# 04_-_SIM800C.net
KiCad netlist of a schematic drawn in Altium Designer
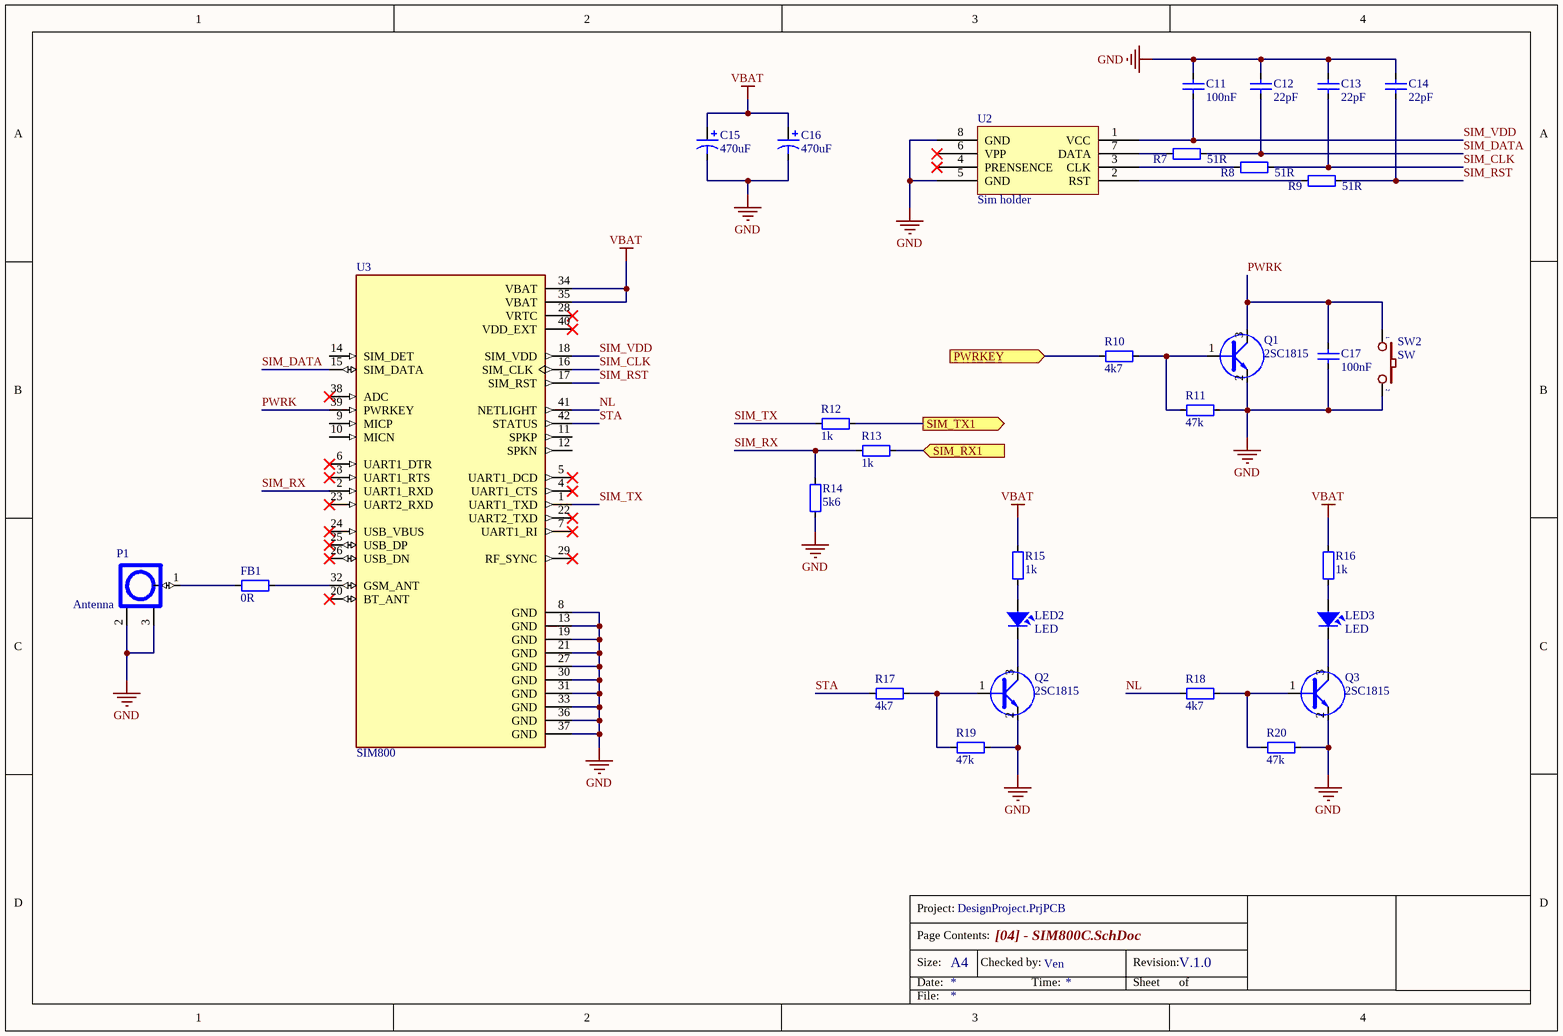
[diagram p0: [04] - SIM800C.SchDoc]

(export (version "E")
  (design (tool "Eeschema 10.0.6"))
  (components
    (comp (ref "C11")
      (value "100nF")
      (footprint "CAP_0603")
      (description "Capacitor")
      (fields (field (name "PUBLISHER") "Altium Limited"))
      (libsource (lib "My Library") (part "CapSMD"))
    )
    (comp (ref "C12")
      (value "22pF")
      (footprint "CAP_0603")
      (description "Capacitor")
      (fields (field (name "PUBLISHER") "Altium Limited"))
      (libsource (lib "My Library") (part "CapSMD"))
    )
    (comp (ref "C13")
      (value "22pF")
      (footprint "CAP_0603")
      (description "Capacitor")
      (fields (field (name "PUBLISHER") "Altium Limited"))
      (libsource (lib "My Library") (part "CapSMD"))
    )
    (comp (ref "C14")
      (value "22pF")
      (footprint "CAP_0603")
      (description "Capacitor")
      (fields (field (name "PUBLISHER") "Altium Limited"))
      (libsource (lib "My Library") (part "CapSMD"))
    )
    (comp (ref "C15")
      (value "470uF")
      (footprint "CAP_7343")
      (description "Polarized Capacitor (Axial)")
      (fields (field (name "PUBLISHER") "Altium Limited"))
      (libsource (lib "My Library") (part "Cap Pol"))
    )
    (comp (ref "C16")
      (value "470uF")
      (footprint "CAP_7343")
      (description "Polarized Capacitor (Axial)")
      (fields (field (name "PUBLISHER") "Altium Limited"))
      (libsource (lib "My Library") (part "Cap Pol"))
    )
    (comp (ref "C17")
      (value "100nF")
      (footprint "CAP_0603")
      (description "Capacitor")
      (fields (field (name "PUBLISHER") "Altium Limited"))
      (libsource (lib "My Library") (part "CapSMD"))
    )
    (comp (ref "FB1")
      (value "0R")
      (footprint "RES-SMD-0603")
      (description "Resistor")
      (fields
        (field (name "MANUFACTURER") "Generic Components")
        (field (name "PUBLISHER") "Altium Hobart Technology Centre")
      )
      (libsource (lib "My Library") (part "Resistor - SMD"))
    )
    (comp (ref "LED2")
      (value "LED")
      (footprint "LED-0805-Green")
      (description "LED Single colour Green and Red")
      (libsource (lib "My Library") (part "LED"))
    )
    (comp (ref "LED3")
      (value "LED")
      (footprint "LED-0805-Green")
      (description "LED Single colour Green and Red")
      (libsource (lib "My Library") (part "LED"))
    )
    (comp (ref "P1")
      (value "Antenna")
      (footprint "IPXS")
      (description "Antenna GSM GPS")
      (libsource (lib "My Library") (part "IPXSx66"))
    )
    (comp (ref "Q1")
      (value "2SC1815")
      (footprint "SOT23")
      (description "NPN 600mW, ECB")
      (libsource (lib "My Library") (part "2SC1815"))
    )
    (comp (ref "Q2")
      (value "2SC1815")
      (footprint "SOT23")
      (description "NPN 600mW, ECB")
      (libsource (lib "My Library") (part "2SC1815"))
    )
    (comp (ref "Q3")
      (value "2SC1815")
      (footprint "SOT23")
      (description "NPN 600mW, ECB")
      (libsource (lib "My Library") (part "2SC1815"))
    )
    (comp (ref "R7")
      (value "51R")
      (footprint "RES-SMD-0603")
      (description "Resistor")
      (fields
        (field (name "MANUFACTURER") "Generic Components")
        (field (name "PUBLISHER") "Altium Hobart Technology Centre")
      )
      (libsource (lib "My Library") (part "Resistor - SMD"))
    )
    (comp (ref "R8")
      (value "51R")
      (footprint "RES-SMD-0603")
      (description "Resistor")
      (fields
        (field (name "MANUFACTURER") "Generic Components")
        (field (name "PUBLISHER") "Altium Hobart Technology Centre")
      )
      (libsource (lib "My Library") (part "Resistor - SMD"))
    )
    (comp (ref "R9")
      (value "51R")
      (footprint "RES-SMD-0603")
      (description "Resistor")
      (fields
        (field (name "MANUFACTURER") "Generic Components")
        (field (name "PUBLISHER") "Altium Hobart Technology Centre")
      )
      (libsource (lib "My Library") (part "Resistor - SMD"))
    )
    (comp (ref "R10")
      (value "4k7")
      (footprint "RES-SMD-0603")
      (description "Resistor")
      (fields
        (field (name "MANUFACTURER") "Generic Components")
        (field (name "PUBLISHER") "Altium Hobart Technology Centre")
      )
      (libsource (lib "My Library") (part "Resistor - SMD"))
    )
    (comp (ref "R11")
      (value "47k")
      (footprint "RES-SMD-0603")
      (description "Resistor")
      (fields
        (field (name "MANUFACTURER") "Generic Components")
        (field (name "PUBLISHER") "Altium Hobart Technology Centre")
      )
      (libsource (lib "My Library") (part "Resistor - SMD"))
    )
    (comp (ref "R12")
      (value "1k")
      (footprint "RES-SMD-0603")
      (description "Resistor")
      (fields
        (field (name "MANUFACTURER") "Generic Components")
        (field (name "PUBLISHER") "Altium Hobart Technology Centre")
      )
      (libsource (lib "My Library") (part "Resistor - SMD"))
    )
    (comp (ref "R13")
      (value "1k")
      (footprint "RES-SMD-0603")
      (description "Resistor")
      (fields
        (field (name "MANUFACTURER") "Generic Components")
        (field (name "PUBLISHER") "Altium Hobart Technology Centre")
      )
      (libsource (lib "My Library") (part "Resistor - SMD"))
    )
    (comp (ref "R14")
      (value "5k6")
      (footprint "RES-SMD-0603")
      (description "Resistor")
      (fields
        (field (name "MANUFACTURER") "Generic Components")
        (field (name "PUBLISHER") "Altium Hobart Technology Centre")
      )
      (libsource (lib "My Library") (part "Resistor - SMD"))
    )
    (comp (ref "R15")
      (value "1k")
      (footprint "RES-SMD-0603")
      (description "Resistor")
      (fields
        (field (name "MANUFACTURER") "Generic Components")
        (field (name "PUBLISHER") "Altium Hobart Technology Centre")
      )
      (libsource (lib "My Library") (part "Resistor - SMD"))
    )
    (comp (ref "R16")
      (value "1k")
      (footprint "RES-SMD-0603")
      (description "Resistor")
      (fields
        (field (name "MANUFACTURER") "Generic Components")
        (field (name "PUBLISHER") "Altium Hobart Technology Centre")
      )
      (libsource (lib "My Library") (part "Resistor - SMD"))
    )
    (comp (ref "R17")
      (value "4k7")
      (footprint "RES-SMD-0603")
      (description "Resistor")
      (fields
        (field (name "MANUFACTURER") "Generic Components")
        (field (name "PUBLISHER") "Altium Hobart Technology Centre")
      )
      (libsource (lib "My Library") (part "Resistor - SMD"))
    )
    (comp (ref "R18")
      (value "4k7")
      (footprint "RES-SMD-0603")
      (description "Resistor")
      (fields
        (field (name "MANUFACTURER") "Generic Components")
        (field (name "PUBLISHER") "Altium Hobart Technology Centre")
      )
      (libsource (lib "My Library") (part "Resistor - SMD"))
    )
    (comp (ref "R19")
      (value "47k")
      (footprint "RES-SMD-0603")
      (description "Resistor")
      (fields
        (field (name "MANUFACTURER") "Generic Components")
        (field (name "PUBLISHER") "Altium Hobart Technology Centre")
      )
      (libsource (lib "My Library") (part "Resistor - SMD"))
    )
    (comp (ref "R20")
      (value "47k")
      (footprint "RES-SMD-0603")
      (description "Resistor")
      (fields
        (field (name "MANUFACTURER") "Generic Components")
        (field (name "PUBLISHER") "Altium Hobart Technology Centre")
      )
      (libsource (lib "My Library") (part "Resistor - SMD"))
    )
    (comp (ref "SW2")
      (value "SW")
      (footprint "SW2")
      (description "Switch button 2 pin")
      (libsource (lib "My Library") (part "SW2"))
    )
    (comp (ref "U2")
      (value "Sim holder")
      (footprint "Sim Socket")
      (description "SIM Card Holder KF-016")
      (fields (field (name "Comment") "SIM-KF016"))
      (libsource (lib "My Library") (part "Sim holder"))
    )
    (comp (ref "U3")
      (value "SIM800")
      (footprint "SIM800C")
      (description "SIM800C IC")
      (libsource (lib "My Library") (part "SIM800C"))
    )
  )
  (nets
    (net (code "1") (name "/NL") (class "Default")
      (node (ref "R18") (pin "1") (pinfunction "1_1") (pintype "passive"))
      (node (ref "U3") (pin "41") (pinfunction "NETLIGHT_41") (pintype "output"))
    )
    (net (code "2") (name "/PWRK") (class "Default")
      (node (ref "C17") (pin "2") (pinfunction "2_2") (pintype "passive"))
      (node (ref "Q1") (pin "3") (pinfunction "C_3") (pintype "passive"))
      (node (ref "SW2") (pin "1") (pinfunction "1_1") (pintype "passive"))
      (node (ref "U3") (pin "39") (pinfunction "PWRKEY_39") (pintype "input"))
    )
    (net (code "3") (name "/PWRKEY") (class "Default")
      (node (ref "R10") (pin "1") (pinfunction "1_1") (pintype "passive"))
    )
    (net (code "4") (name "/SIM_CLK") (class "Default")
      (node (ref "C13") (pin "1") (pinfunction "1_1") (pintype "passive"))
      (node (ref "R8") (pin "2") (pinfunction "2_2") (pintype "passive"))
      (node (ref "U3") (pin "16") (pinfunction "SIM_CLK_16") (pintype "output"))
    )
    (net (code "5") (name "/SIM_DATA") (class "Default")
      (node (ref "C12") (pin "1") (pinfunction "1_1") (pintype "passive"))
      (node (ref "R7") (pin "2") (pinfunction "2_2") (pintype "passive"))
      (node (ref "U3") (pin "15") (pinfunction "SIM_DATA_15") (pintype "bidirectional"))
    )
    (net (code "6") (name "/SIM_RST") (class "Default")
      (node (ref "C14") (pin "1") (pinfunction "1_1") (pintype "passive"))
      (node (ref "R9") (pin "2") (pinfunction "2_2") (pintype "passive"))
      (node (ref "U3") (pin "17") (pinfunction "SIM_RST_17") (pintype "output"))
    )
    (net (code "7") (name "/SIM_RX") (class "Default")
      (node (ref "R13") (pin "2") (pinfunction "2_2") (pintype "passive"))
      (node (ref "R14") (pin "2") (pinfunction "2_2") (pintype "passive"))
      (node (ref "U3") (pin "2") (pinfunction "UART1_RXD_2") (pintype "input"))
    )
    (net (code "8") (name "/SIM_RX1") (class "Default")
      (node (ref "R13") (pin "1") (pinfunction "1_1") (pintype "passive"))
    )
    (net (code "9") (name "/SIM_TX") (class "Default")
      (node (ref "R12") (pin "2") (pinfunction "2_2") (pintype "passive"))
      (node (ref "U3") (pin "1") (pinfunction "UART1_TXD_1") (pintype "output"))
    )
    (net (code "10") (name "/SIM_TX1") (class "Default")
      (node (ref "R12") (pin "1") (pinfunction "1_1") (pintype "passive"))
    )
    (net (code "11") (name "/SIM_VDD") (class "Default")
      (node (ref "C11") (pin "1") (pinfunction "1_1") (pintype "passive"))
      (node (ref "U2") (pin "1") (pinfunction "VCC_1") (pintype "passive"))
      (node (ref "U3") (pin "18") (pinfunction "SIM_VDD_18") (pintype "output"))
    )
    (net (code "12") (name "/STA") (class "Default")
      (node (ref "R17") (pin "1") (pinfunction "1_1") (pintype "passive"))
      (node (ref "U3") (pin "42") (pinfunction "STATUS_42") (pintype "output"))
    )
    (net (code "13") (name "GND") (class "Default")
      (node (ref "C11") (pin "2") (pinfunction "2_2") (pintype "passive"))
      (node (ref "C12") (pin "2") (pinfunction "2_2") (pintype "passive"))
      (node (ref "C13") (pin "2") (pinfunction "2_2") (pintype "passive"))
      (node (ref "C14") (pin "2") (pinfunction "2_2") (pintype "passive"))
      (node (ref "C15") (pin "2") (pinfunction "2_2") (pintype "passive"))
      (node (ref "C16") (pin "2") (pinfunction "2_2") (pintype "passive"))
      (node (ref "C17") (pin "1") (pinfunction "1_1") (pintype "passive"))
      (node (ref "P1") (pin "2") (pintype "passive"))
      (node (ref "P1") (pin "3") (pintype "passive"))
      (node (ref "Q1") (pin "2") (pinfunction "E_2") (pintype "passive"))
      (node (ref "Q2") (pin "2") (pinfunction "E_2") (pintype "passive"))
      (node (ref "Q3") (pin "2") (pinfunction "E_2") (pintype "passive"))
      (node (ref "R11") (pin "2") (pinfunction "2_2") (pintype "passive"))
      (node (ref "R14") (pin "1") (pinfunction "1_1") (pintype "passive"))
      (node (ref "R19") (pin "2") (pinfunction "2_2") (pintype "passive"))
      (node (ref "R20") (pin "2") (pinfunction "2_2") (pintype "passive"))
      (node (ref "SW2") (pin "2") (pinfunction "2_2") (pintype "passive"))
      (node (ref "U2") (pin "5") (pinfunction "GND_5") (pintype "passive"))
      (node (ref "U2") (pin "8") (pinfunction "GND_8") (pintype "passive"))
      (node (ref "U3") (pin "13") (pinfunction "GND_13") (pintype "power_in"))
      (node (ref "U3") (pin "19") (pinfunction "GND_19") (pintype "power_in"))
      (node (ref "U3") (pin "21") (pinfunction "GND_21") (pintype "power_in"))
      (node (ref "U3") (pin "27") (pinfunction "GND_27") (pintype "power_in"))
      (node (ref "U3") (pin "30") (pinfunction "GND_30") (pintype "power_in"))
      (node (ref "U3") (pin "31") (pinfunction "GND_31") (pintype "power_in"))
      (node (ref "U3") (pin "33") (pinfunction "GND_33") (pintype "power_in"))
      (node (ref "U3") (pin "36") (pinfunction "GND_36") (pintype "power_in"))
      (node (ref "U3") (pin "37") (pinfunction "GND_37") (pintype "power_in"))
      (node (ref "U3") (pin "8") (pinfunction "GND_8") (pintype "power_in"))
    )
    (net (code "14") (name "Net-(FB1-Pad1)") (class "Default")
      (node (ref "FB1") (pin "1") (pinfunction "1_1") (pintype "passive"))
      (node (ref "P1") (pin "1") (pintype "bidirectional"))
    )
    (net (code "15") (name "Net-(LED2-Pad1)") (class "Default")
      (node (ref "LED2") (pin "1") (pinfunction "1_1") (pintype "passive"))
      (node (ref "R15") (pin "1") (pinfunction "1_1") (pintype "passive"))
    )
    (net (code "16") (name "Net-(LED3-Pad1)") (class "Default")
      (node (ref "LED3") (pin "1") (pinfunction "1_1") (pintype "passive"))
      (node (ref "R16") (pin "1") (pinfunction "1_1") (pintype "passive"))
    )
    (net (code "17") (name "Net-(Q1-B)") (class "Default")
      (node (ref "Q1") (pin "1") (pinfunction "B_1") (pintype "passive"))
      (node (ref "R10") (pin "2") (pinfunction "2_2") (pintype "passive"))
      (node (ref "R11") (pin "1") (pinfunction "1_1") (pintype "passive"))
    )
    (net (code "18") (name "Net-(Q2-B)") (class "Default")
      (node (ref "Q2") (pin "1") (pinfunction "B_1") (pintype "passive"))
      (node (ref "R17") (pin "2") (pinfunction "2_2") (pintype "passive"))
      (node (ref "R19") (pin "1") (pinfunction "1_1") (pintype "passive"))
    )
    (net (code "19") (name "Net-(Q2-C)") (class "Default")
      (node (ref "LED2") (pin "2") (pinfunction "2_2") (pintype "passive"))
      (node (ref "Q2") (pin "3") (pinfunction "C_3") (pintype "passive"))
    )
    (net (code "20") (name "Net-(Q3-B)") (class "Default")
      (node (ref "Q3") (pin "1") (pinfunction "B_1") (pintype "passive"))
      (node (ref "R18") (pin "2") (pinfunction "2_2") (pintype "passive"))
      (node (ref "R20") (pin "1") (pinfunction "1_1") (pintype "passive"))
    )
    (net (code "21") (name "Net-(Q3-C)") (class "Default")
      (node (ref "LED3") (pin "2") (pinfunction "2_2") (pintype "passive"))
      (node (ref "Q3") (pin "3") (pinfunction "C_3") (pintype "passive"))
    )
    (net (code "22") (name "Net-(U2-CLK)") (class "Default")
      (node (ref "R8") (pin "1") (pinfunction "1_1") (pintype "passive"))
      (node (ref "U2") (pin "3") (pinfunction "CLK_3") (pintype "passive"))
    )
    (net (code "23") (name "Net-(U2-DATA)") (class "Default")
      (node (ref "R7") (pin "1") (pinfunction "1_1") (pintype "passive"))
      (node (ref "U2") (pin "7") (pinfunction "DATA_7") (pintype "passive"))
    )
    (net (code "24") (name "Net-(U2-RST)") (class "Default")
      (node (ref "R9") (pin "1") (pinfunction "1_1") (pintype "passive"))
      (node (ref "U2") (pin "2") (pinfunction "RST_2") (pintype "passive"))
    )
    (net (code "25") (name "Net-(U3-GSM_ANT)") (class "Default")
      (node (ref "FB1") (pin "2") (pinfunction "2_2") (pintype "passive"))
      (node (ref "U3") (pin "32") (pinfunction "GSM_ANT_32") (pintype "bidirectional"))
    )
    (net (code "26") (name "VBAT") (class "Default")
      (node (ref "C15") (pin "1") (pinfunction "1_1") (pintype "passive"))
      (node (ref "C16") (pin "1") (pinfunction "1_1") (pintype "passive"))
      (node (ref "R15") (pin "2") (pinfunction "2_2") (pintype "passive"))
      (node (ref "R16") (pin "2") (pinfunction "2_2") (pintype "passive"))
      (node (ref "U3") (pin "34") (pinfunction "VBAT_34") (pintype "power_in"))
      (node (ref "U3") (pin "35") (pinfunction "VBAT_35") (pintype "power_in"))
    )
    (net (code "27") (name "unconnected-(U2-PRENSENCE-Pad4)") (class "Default")
      (node (ref "U2") (pin "4") (pinfunction "PRENSENCE_4") (pintype "passive+no_connect"))
    )
    (net (code "28") (name "unconnected-(U2-VPP-Pad6)") (class "Default")
      (node (ref "U2") (pin "6") (pinfunction "VPP_6") (pintype "passive+no_connect"))
    )
    (net (code "29") (name "unconnected-(U3-ADC-Pad38)") (class "Default")
      (node (ref "U3") (pin "38") (pinfunction "ADC_38") (pintype "input+no_connect"))
    )
    (net (code "30") (name "unconnected-(U3-BT_ANT-Pad20)") (class "Default")
      (node (ref "U3") (pin "20") (pinfunction "BT_ANT_20") (pintype "bidirectional+no_connect"))
    )
    (net (code "31") (name "unconnected-(U3-MICN-Pad10)") (class "Default")
      (node (ref "U3") (pin "10") (pinfunction "MICN_10") (pintype "input"))
    )
    (net (code "32") (name "unconnected-(U3-MICP-Pad9)") (class "Default")
      (node (ref "U3") (pin "9") (pinfunction "MICP_9") (pintype "input"))
    )
    (net (code "33") (name "unconnected-(U3-RF_SYNC-Pad29)") (class "Default")
      (node (ref "U3") (pin "29") (pinfunction "RF_SYNC_29") (pintype "output+no_connect"))
    )
    (net (code "34") (name "unconnected-(U3-SIM_DET-Pad14)") (class "Default")
      (node (ref "U3") (pin "14") (pinfunction "SIM_DET_14") (pintype "input"))
    )
    (net (code "35") (name "unconnected-(U3-SPKN-Pad12)") (class "Default")
      (node (ref "U3") (pin "12") (pinfunction "SPKN_12") (pintype "output"))
    )
    (net (code "36") (name "unconnected-(U3-SPKP-Pad11)") (class "Default")
      (node (ref "U3") (pin "11") (pinfunction "SPKP_11") (pintype "output"))
    )
    (net (code "37") (name "unconnected-(U3-UART1_CTS-Pad4)") (class "Default")
      (node (ref "U3") (pin "4") (pinfunction "UART1_CTS_4") (pintype "output+no_connect"))
    )
    (net (code "38") (name "unconnected-(U3-UART1_DCD-Pad5)") (class "Default")
      (node (ref "U3") (pin "5") (pinfunction "UART1_DCD_5") (pintype "output+no_connect"))
    )
    (net (code "39") (name "unconnected-(U3-UART1_DTR-Pad6)") (class "Default")
      (node (ref "U3") (pin "6") (pinfunction "UART1_DTR_6") (pintype "input+no_connect"))
    )
    (net (code "40") (name "unconnected-(U3-UART1_RI-Pad7)") (class "Default")
      (node (ref "U3") (pin "7") (pinfunction "UART1_RI_7") (pintype "output+no_connect"))
    )
    (net (code "41") (name "unconnected-(U3-UART1_RTS-Pad3)") (class "Default")
      (node (ref "U3") (pin "3") (pinfunction "UART1_RTS_3") (pintype "input+no_connect"))
    )
    (net (code "42") (name "unconnected-(U3-UART2_RXD-Pad23)") (class "Default")
      (node (ref "U3") (pin "23") (pinfunction "UART2_RXD_23") (pintype "input+no_connect"))
    )
    (net (code "43") (name "unconnected-(U3-UART2_TXD-Pad22)") (class "Default")
      (node (ref "U3") (pin "22") (pinfunction "UART2_TXD_22") (pintype "output+no_connect"))
    )
    (net (code "44") (name "unconnected-(U3-USB_DN-Pad26)") (class "Default")
      (node (ref "U3") (pin "26") (pinfunction "USB_DN_26") (pintype "bidirectional+no_connect"))
    )
    (net (code "45") (name "unconnected-(U3-USB_DP-Pad25)") (class "Default")
      (node (ref "U3") (pin "25") (pinfunction "USB_DP_25") (pintype "bidirectional+no_connect"))
    )
    (net (code "46") (name "unconnected-(U3-USB_VBUS-Pad24)") (class "Default")
      (node (ref "U3") (pin "24") (pinfunction "USB_VBUS_24") (pintype "input+no_connect"))
    )
    (net (code "47") (name "unconnected-(U3-VDD_EXT-Pad40)") (class "Default")
      (node (ref "U3") (pin "40") (pinfunction "VDD_EXT_40") (pintype "power_in+no_connect"))
    )
    (net (code "48") (name "unconnected-(U3-VRTC-Pad28)") (class "Default")
      (node (ref "U3") (pin "28") (pinfunction "VRTC_28") (pintype "power_in+no_connect"))
    )
  )
)
